# 07_AC97_AUDIO.net
KiCad netlist of a schematic drawn in Altium Designer
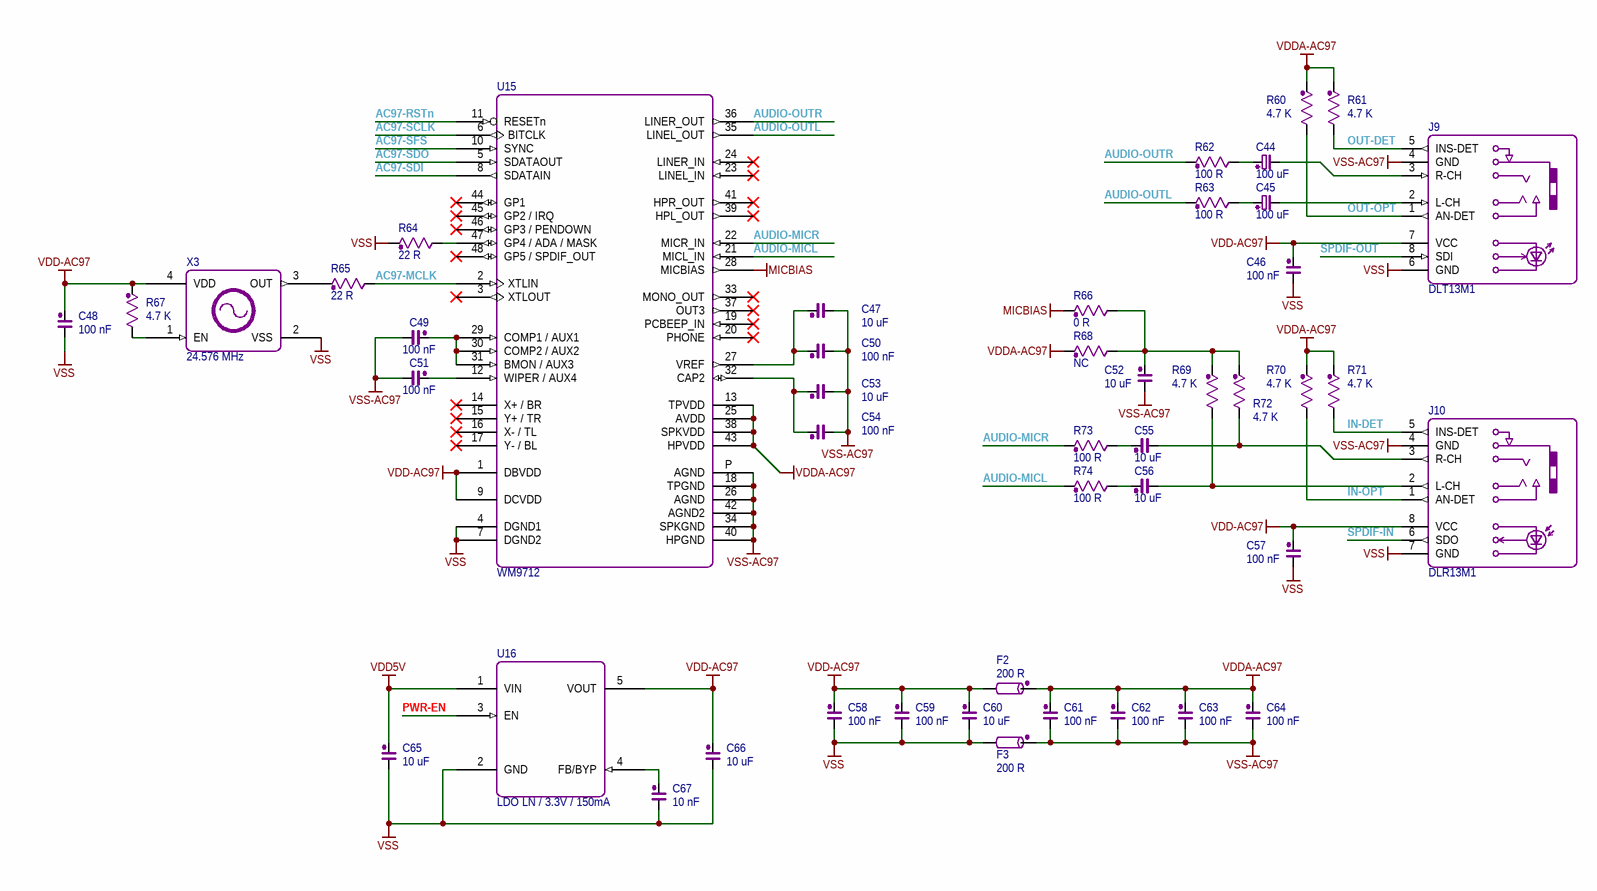
[diagram p0: 07_AC97_AUDIO.SchDoc]

(export (version "E")
  (design (tool "Eeschema 10.0.6"))
  (components
    (comp (ref "C44")
      (value "100 uF")
      (footprint "CAP_EB")
      (description "Electrolyte Capacitor")
      (fields
        (field (name "PARTNUMBER") "0")
        (field (name "DESIGNER") "shyul")
        (field (name "PUBLISHER") "Cowin")
      )
      (libsource (lib "Basc_1_Passive") (part "CAP_E"))
    )
    (comp (ref "C45")
      (value "100 uF")
      (footprint "CAP_EB")
      (description "Electrolyte Capacitor")
      (fields
        (field (name "PARTNUMBER") "0")
        (field (name "DESIGNER") "shyul")
        (field (name "PUBLISHER") "Cowin")
      )
      (libsource (lib "Basc_1_Passive") (part "CAP_E"))
    )
    (comp (ref "C46")
      (value "100 nF")
      (footprint "0603A1")
      (description "Normal Capacitor")
      (fields
        (field (name "PARTNUMBER") "0")
        (field (name "PUBLISHER") "Cowin")
        (field (name "DESIGNER") "shyul")
      )
      (libsource (lib "") (part "CAP_1"))
    )
    (comp (ref "C47")
      (value "10 uF")
      (footprint "0603A1")
      (description "Normal Capacitor")
      (fields
        (field (name "PARTNUMBER") "0")
        (field (name "PUBLISHER") "Cowin")
        (field (name "DESIGNER") "shyul")
      )
      (libsource (lib "Basc_1_Passive") (part "CAP"))
    )
    (comp (ref "C48")
      (value "100 nF")
      (footprint "0402A1")
      (description "Normal Capacitor")
      (fields
        (field (name "PARTNUMBER") "0")
        (field (name "PUBLISHER") "Cowin")
        (field (name "DESIGNER") "shyul")
      )
      (libsource (lib "") (part "CAP_1"))
    )
    (comp (ref "C49")
      (value "100 nF")
      (footprint "0402A1")
      (description "Normal Capacitor")
      (fields
        (field (name "PARTNUMBER") "0")
        (field (name "PUBLISHER") "Cowin")
        (field (name "DESIGNER") "shyul")
      )
      (libsource (lib "") (part "CAP_2"))
    )
    (comp (ref "C50")
      (value "100 nF")
      (footprint "0402A1")
      (description "Normal Capacitor")
      (fields
        (field (name "PARTNUMBER") "0")
        (field (name "PUBLISHER") "Cowin")
        (field (name "DESIGNER") "shyul")
      )
      (libsource (lib "Basc_1_Passive") (part "CAP"))
    )
    (comp (ref "C51")
      (value "100 nF")
      (footprint "0402A1")
      (description "Normal Capacitor")
      (fields
        (field (name "PARTNUMBER") "0")
        (field (name "PUBLISHER") "Cowin")
        (field (name "DESIGNER") "shyul")
      )
      (libsource (lib "") (part "CAP_2"))
    )
    (comp (ref "C52")
      (value "10 uF")
      (footprint "0603A1")
      (description "Normal Capacitor")
      (fields
        (field (name "PARTNUMBER") "0")
        (field (name "PUBLISHER") "Cowin")
        (field (name "DESIGNER") "shyul")
      )
      (libsource (lib "") (part "CAP_1"))
    )
    (comp (ref "C53")
      (value "10 uF")
      (footprint "0603A1")
      (description "Normal Capacitor")
      (fields
        (field (name "PARTNUMBER") "0")
        (field (name "PUBLISHER") "Cowin")
        (field (name "DESIGNER") "shyul")
      )
      (libsource (lib "Basc_1_Passive") (part "CAP"))
    )
    (comp (ref "C54")
      (value "100 nF")
      (footprint "0402A1")
      (description "Normal Capacitor")
      (fields
        (field (name "PARTNUMBER") "0")
        (field (name "PUBLISHER") "Cowin")
        (field (name "DESIGNER") "shyul")
      )
      (libsource (lib "Basc_1_Passive") (part "CAP"))
    )
    (comp (ref "C55")
      (value "10 uF")
      (footprint "1210A1")
      (description "Normal Capacitor")
      (fields
        (field (name "PARTNUMBER") "0")
        (field (name "PUBLISHER") "Cowin")
        (field (name "DESIGNER") "shyul")
      )
      (libsource (lib "Basc_1_Passive") (part "CAP"))
    )
    (comp (ref "C56")
      (value "10 uF")
      (footprint "1210A1")
      (description "Normal Capacitor")
      (fields
        (field (name "PARTNUMBER") "0")
        (field (name "PUBLISHER") "Cowin")
        (field (name "DESIGNER") "shyul")
      )
      (libsource (lib "Basc_1_Passive") (part "CAP"))
    )
    (comp (ref "C57")
      (value "100 nF")
      (footprint "0603A1")
      (description "Normal Capacitor")
      (fields
        (field (name "PARTNUMBER") "0")
        (field (name "PUBLISHER") "Cowin")
        (field (name "DESIGNER") "shyul")
      )
      (libsource (lib "") (part "CAP_1"))
    )
    (comp (ref "C58")
      (value "100 nF")
      (footprint "0402A1")
      (description "Normal Capacitor")
      (fields
        (field (name "PARTNUMBER") "0")
        (field (name "PUBLISHER") "Cowin")
        (field (name "DESIGNER") "shyul")
      )
      (libsource (lib "") (part "CAP_1"))
    )
    (comp (ref "C59")
      (value "100 nF")
      (footprint "0402A1")
      (description "Normal Capacitor")
      (fields
        (field (name "PARTNUMBER") "0")
        (field (name "PUBLISHER") "Cowin")
        (field (name "DESIGNER") "shyul")
      )
      (libsource (lib "") (part "CAP_1"))
    )
    (comp (ref "C60")
      (value "10 uF")
      (footprint "0603A1")
      (description "Normal Capacitor")
      (fields
        (field (name "PARTNUMBER") "0")
        (field (name "PUBLISHER") "Cowin")
        (field (name "DESIGNER") "shyul")
      )
      (libsource (lib "") (part "CAP_1"))
    )
    (comp (ref "C61")
      (value "100 nF")
      (footprint "0402A1")
      (description "Normal Capacitor")
      (fields
        (field (name "PARTNUMBER") "0")
        (field (name "PUBLISHER") "Cowin")
        (field (name "DESIGNER") "shyul")
      )
      (libsource (lib "") (part "CAP_1"))
    )
    (comp (ref "C62")
      (value "100 nF")
      (footprint "0402A1")
      (description "Normal Capacitor")
      (fields
        (field (name "PARTNUMBER") "0")
        (field (name "PUBLISHER") "Cowin")
        (field (name "DESIGNER") "shyul")
      )
      (libsource (lib "") (part "CAP_1"))
    )
    (comp (ref "C63")
      (value "100 nF")
      (footprint "0402A1")
      (description "Normal Capacitor")
      (fields
        (field (name "PARTNUMBER") "0")
        (field (name "PUBLISHER") "Cowin")
        (field (name "DESIGNER") "shyul")
      )
      (libsource (lib "") (part "CAP_1"))
    )
    (comp (ref "C64")
      (value "100 nF")
      (footprint "0402A1")
      (description "Normal Capacitor")
      (fields
        (field (name "PARTNUMBER") "0")
        (field (name "PUBLISHER") "Cowin")
        (field (name "DESIGNER") "shyul")
      )
      (libsource (lib "") (part "CAP_1"))
    )
    (comp (ref "C65")
      (value "10 uF")
      (footprint "0603A1")
      (description "Normal Capacitor")
      (fields
        (field (name "PARTNUMBER") "0")
        (field (name "PUBLISHER") "Cowin")
        (field (name "DESIGNER") "shyul")
      )
      (libsource (lib "") (part "CAP_1"))
    )
    (comp (ref "C66")
      (value "10 uF")
      (footprint "0603A1")
      (description "Normal Capacitor")
      (fields
        (field (name "PARTNUMBER") "0")
        (field (name "PUBLISHER") "Cowin")
        (field (name "DESIGNER") "shyul")
      )
      (libsource (lib "") (part "CAP_1"))
    )
    (comp (ref "C67")
      (value "10 nF")
      (footprint "0402A1")
      (description "Normal Capacitor")
      (fields
        (field (name "PARTNUMBER") "0")
        (field (name "PUBLISHER") "Cowin")
        (field (name "DESIGNER") "shyul")
      )
      (libsource (lib "") (part "CAP_1"))
    )
    (comp (ref "F2")
      (value "200 R")
      (footprint "0603A3")
      (description "EMI Bead")
      (fields
        (field (name "PARTNUMBER") "BLM")
        (field (name "DESIGNER") "shyul")
        (field (name "PUBLISHER") "Cowin")
      )
      (libsource (lib "Basc_2_EMI_Protection") (part "BEAD"))
    )
    (comp (ref "F3")
      (value "200 R")
      (footprint "0603A3")
      (description "EMI Bead")
      (fields
        (field (name "PARTNUMBER") "BLM")
        (field (name "DESIGNER") "shyul")
        (field (name "PUBLISHER") "Cowin")
      )
      (libsource (lib "Basc_2_EMI_Protection") (part "BEAD"))
    )
    (comp (ref "J9")
      (value "DLT13M1")
      (footprint "DLT13M1")
      (description "3.5mm Audio Jack with SPDIF Optical Output")
      (fields (field (name "PUBLISHER") "Cowin") (field (name "DESIGNER") "shyul"))
      (libsource (lib "PCB_MDB-U01") (part "DLT13M1"))
    )
    (comp (ref "J10")
      (value "DLR13M1")
      (footprint "DLR13M1")
      (description "3.5mm Audio Jack with SPDIF Optical Input")
      (fields (field (name "PUBLISHER") "Cowin") (field (name "DESIGNER") "shyul"))
      (libsource (lib "PCB_MDB-U01") (part "DLR13M1"))
    )
    (comp (ref "R60")
      (value "4.7 K")
      (footprint "0603A2")
      (description "Normal Resistor")
      (fields
        (field (name "PARTNUMBER") "0")
        (field (name "DESIGNER") "shyul")
        (field (name "PUBLISHER") "Cowin")
      )
      (libsource (lib "Basc_1_Passive") (part "RES"))
    )
    (comp (ref "R61")
      (value "4.7 K")
      (footprint "0603A2")
      (description "Normal Resistor")
      (fields
        (field (name "PARTNUMBER") "0")
        (field (name "DESIGNER") "shyul")
        (field (name "PUBLISHER") "Cowin")
      )
      (libsource (lib "Basc_1_Passive") (part "RES"))
    )
    (comp (ref "R62")
      (value "100 R")
      (footprint "0603A2")
      (description "Normal Resistor")
      (fields
        (field (name "PARTNUMBER") "0")
        (field (name "DESIGNER") "shyul")
        (field (name "PUBLISHER") "Cowin")
      )
      (libsource (lib "Basc_1_Passive") (part "RES"))
    )
    (comp (ref "R63")
      (value "100 R")
      (footprint "0603A2")
      (description "Normal Resistor")
      (fields
        (field (name "PARTNUMBER") "0")
        (field (name "DESIGNER") "shyul")
        (field (name "PUBLISHER") "Cowin")
      )
      (libsource (lib "Basc_1_Passive") (part "RES"))
    )
    (comp (ref "R64")
      (value "22 R")
      (footprint "0402A2")
      (description "Normal Resistor")
      (fields
        (field (name "PARTNUMBER") "0")
        (field (name "DESIGNER") "shyul")
        (field (name "PUBLISHER") "Cowin")
      )
      (libsource (lib "Basc_1_Passive") (part "RES"))
    )
    (comp (ref "R65")
      (value "22 R")
      (footprint "0402A2")
      (description "Normal Resistor")
      (fields
        (field (name "PARTNUMBER") "0")
        (field (name "DESIGNER") "shyul")
        (field (name "PUBLISHER") "Cowin")
      )
      (libsource (lib "Basc_1_Passive") (part "RES"))
    )
    (comp (ref "R66")
      (value "0 R")
      (footprint "0603A2")
      (description "Normal Resistor")
      (fields
        (field (name "PARTNUMBER") "0")
        (field (name "DESIGNER") "shyul")
        (field (name "PUBLISHER") "Cowin")
      )
      (libsource (lib "Basc_1_Passive") (part "RES"))
    )
    (comp (ref "R67")
      (value "4.7 K")
      (footprint "0402A2")
      (description "Normal Resistor")
      (fields
        (field (name "PARTNUMBER") "0")
        (field (name "DESIGNER") "shyul")
        (field (name "PUBLISHER") "Cowin")
      )
      (libsource (lib "Basc_1_Passive") (part "RES"))
    )
    (comp (ref "R68")
      (value "NC")
      (footprint "0603A2")
      (description "Normal Resistor")
      (fields
        (field (name "PARTNUMBER") "0")
        (field (name "DESIGNER") "shyul")
        (field (name "PUBLISHER") "Cowin")
      )
      (libsource (lib "Basc_1_Passive") (part "RES"))
    )
    (comp (ref "R69")
      (value "4.7 K")
      (footprint "0603A2")
      (description "Normal Resistor")
      (fields
        (field (name "PARTNUMBER") "0")
        (field (name "DESIGNER") "shyul")
        (field (name "PUBLISHER") "Cowin")
      )
      (libsource (lib "Basc_1_Passive") (part "RES"))
    )
    (comp (ref "R70")
      (value "4.7 K")
      (footprint "0603A2")
      (description "Normal Resistor")
      (fields
        (field (name "PARTNUMBER") "0")
        (field (name "DESIGNER") "shyul")
        (field (name "PUBLISHER") "Cowin")
      )
      (libsource (lib "Basc_1_Passive") (part "RES"))
    )
    (comp (ref "R71")
      (value "4.7 K")
      (footprint "0603A2")
      (description "Normal Resistor")
      (fields
        (field (name "PARTNUMBER") "0")
        (field (name "DESIGNER") "shyul")
        (field (name "PUBLISHER") "Cowin")
      )
      (libsource (lib "Basc_1_Passive") (part "RES"))
    )
    (comp (ref "R72")
      (value "4.7 K")
      (footprint "0603A2")
      (description "Normal Resistor")
      (fields
        (field (name "PARTNUMBER") "0")
        (field (name "DESIGNER") "shyul")
        (field (name "PUBLISHER") "Cowin")
      )
      (libsource (lib "Basc_1_Passive") (part "RES"))
    )
    (comp (ref "R73")
      (value "100 R")
      (footprint "0603A2")
      (description "Normal Resistor")
      (fields
        (field (name "PARTNUMBER") "0")
        (field (name "DESIGNER") "shyul")
        (field (name "PUBLISHER") "Cowin")
      )
      (libsource (lib "Basc_1_Passive") (part "RES"))
    )
    (comp (ref "R74")
      (value "100 R")
      (footprint "0603A2")
      (description "Normal Resistor")
      (fields
        (field (name "PARTNUMBER") "0")
        (field (name "DESIGNER") "shyul")
        (field (name "PUBLISHER") "Cowin")
      )
      (libsource (lib "Basc_1_Passive") (part "RES"))
    )
    (comp (ref "U15")
      (value "WM9712")
      (footprint "QFN-7-48")
      (description "WM9712 AC97 Codec")
      (fields
        (field (name "PARTNUMBER") "WM9712LGEFL")
        (field (name "PUBLISHER") "Cowin")
        (field (name "DESIGNER") "shyul")
      )
      (libsource (lib "PCB_LDB-U01") (part "WM9712"))
    )
    (comp (ref "U16")
      (value "LDO LN / 3.3V / 150mA")
      (footprint "SOT-23-5")
      (description "Low Noise LDO 150mA")
      (fields
        (field (name "PARTNUMBER") "MIC5265-3.3YD5")
        (field (name "PUBLISHER") "Cowin")
        (field (name "DESIGNER") "shyul")
      )
      (libsource (lib "IC_10_Regulator") (part "MIC5265"))
    )
    (comp (ref "X3")
      (value "24.576 MHz")
      (footprint "OSC_4B_S_5032")
      (description "Crystal Oscillator")
      (fields
        (field (name "PARTNUMBER") "0")
        (field (name "PUBLISHER") "Cowin")
        (field (name "DESIGNER") "shyul")
      )
      (libsource (lib "Basc_4_Other") (part "OSC_4B"))
    )
  )
  (nets
    (net (code "1") (name "/AC97-MCLK") (class "Default")
      (node (ref "R65") (pin "1") (pinfunction "1_1") (pintype "passive"))
      (node (ref "U15") (pin "2") (pinfunction "XTLIN_2") (pintype "input"))
    )
    (net (code "2") (name "/AC97-RSTn") (class "Default")
      (node (ref "U15") (pin "11") (pinfunction "RESETn_11") (pintype "input"))
    )
    (net (code "3") (name "/AC97-SCLK") (class "Default")
      (node (ref "U15") (pin "6") (pinfunction "BITCLK_6") (pintype "output"))
    )
    (net (code "4") (name "/AC97-SDI") (class "Default")
      (node (ref "U15") (pin "8") (pinfunction "SDATAIN_8") (pintype "output"))
    )
    (net (code "5") (name "/AC97-SDO") (class "Default")
      (node (ref "U15") (pin "5") (pinfunction "SDATAOUT_5") (pintype "input"))
    )
    (net (code "6") (name "/AC97-SFS") (class "Default")
      (node (ref "U15") (pin "10") (pinfunction "SYNC_10") (pintype "input"))
    )
    (net (code "7") (name "/AUDIO-MICL") (class "Default")
      (node (ref "R74") (pin "2") (pinfunction "2_2") (pintype "passive"))
      (node (ref "U15") (pin "21") (pinfunction "MICL_IN_21") (pintype "input"))
    )
    (net (code "8") (name "/AUDIO-MICR") (class "Default")
      (node (ref "R73") (pin "2") (pinfunction "2_2") (pintype "passive"))
      (node (ref "U15") (pin "22") (pinfunction "MICR_IN_22") (pintype "input"))
    )
    (net (code "9") (name "/AUDIO-OUTL") (class "Default")
      (node (ref "R63") (pin "2") (pinfunction "2_2") (pintype "passive"))
      (node (ref "U15") (pin "35") (pinfunction "LINEL_OUT_35") (pintype "output"))
    )
    (net (code "10") (name "/AUDIO-OUTR") (class "Default")
      (node (ref "R62") (pin "2") (pinfunction "2_2") (pintype "passive"))
      (node (ref "U15") (pin "36") (pinfunction "LINER_OUT_36") (pintype "output"))
    )
    (net (code "11") (name "/IN-DET") (class "Default")
      (node (ref "J10") (pin "5") (pinfunction "INS-DET_5") (pintype "output"))
      (node (ref "R71") (pin "1") (pinfunction "1_1") (pintype "passive"))
    )
    (net (code "12") (name "/IN-OPT") (class "Default")
      (node (ref "J10") (pin "1") (pinfunction "AN-DET_1") (pintype "output"))
      (node (ref "R70") (pin "1") (pinfunction "1_1") (pintype "passive"))
    )
    (net (code "13") (name "/OUT-DET") (class "Default")
      (node (ref "J9") (pin "5") (pinfunction "INS-DET_5") (pintype "output"))
      (node (ref "R61") (pin "1") (pinfunction "1_1") (pintype "passive"))
    )
    (net (code "14") (name "/OUT-OPT") (class "Default")
      (node (ref "J9") (pin "1") (pinfunction "AN-DET_1") (pintype "output"))
      (node (ref "R60") (pin "1") (pinfunction "1_1") (pintype "passive"))
    )
    (net (code "15") (name "/PWR-EN") (class "Default")
      (node (ref "U16") (pin "3") (pinfunction "EN_3") (pintype "input"))
    )
    (net (code "16") (name "/SPDIF-IN") (class "Default")
      (node (ref "J10") (pin "6") (pinfunction "SDO_6") (pintype "output"))
    )
    (net (code "17") (name "/SPDIF-OUT") (class "Default")
      (node (ref "J9") (pin "8") (pinfunction "SDI_8") (pintype "input"))
    )
    (net (code "18") (name "MICBIAS") (class "Default")
      (node (ref "R66") (pin "2") (pinfunction "2_2") (pintype "passive"))
      (node (ref "U15") (pin "28") (pinfunction "MICBIAS_28") (pintype "output"))
    )
    (net (code "19") (name "Net-(C44-Pad2)") (class "Default")
      (node (ref "C44") (pin "2") (pinfunction "2_2") (pintype "passive"))
      (node (ref "R62") (pin "1") (pinfunction "1_1") (pintype "passive"))
    )
    (net (code "20") (name "Net-(C45-Pad2)") (class "Default")
      (node (ref "C45") (pin "2") (pinfunction "2_2") (pintype "passive"))
      (node (ref "R63") (pin "1") (pinfunction "1_1") (pintype "passive"))
    )
    (net (code "21") (name "Net-(C52-Pad2)") (class "Default")
      (node (ref "C52") (pin "2") (pinfunction "2_2") (pintype "passive"))
      (node (ref "R66") (pin "1") (pinfunction "1_1") (pintype "passive"))
      (node (ref "R68") (pin "1") (pinfunction "1_1") (pintype "passive"))
      (node (ref "R69") (pin "2") (pinfunction "2_2") (pintype "passive"))
      (node (ref "R72") (pin "2") (pinfunction "2_2") (pintype "passive"))
    )
    (net (code "22") (name "Net-(C55-Pad2)") (class "Default")
      (node (ref "C55") (pin "2") (pinfunction "2_2") (pintype "passive"))
      (node (ref "R73") (pin "1") (pinfunction "1_1") (pintype "passive"))
    )
    (net (code "23") (name "Net-(C56-Pad2)") (class "Default")
      (node (ref "C56") (pin "2") (pinfunction "2_2") (pintype "passive"))
      (node (ref "R74") (pin "1") (pinfunction "1_1") (pintype "passive"))
    )
    (net (code "24") (name "Net-(J9-L-CH)") (class "Default")
      (node (ref "C45") (pin "1") (pinfunction "1_1") (pintype "passive"))
      (node (ref "J9") (pin "2") (pinfunction "L-CH_2") (pintype "input"))
    )
    (net (code "25") (name "Net-(J9-R-CH)") (class "Default")
      (node (ref "C44") (pin "1") (pinfunction "1_1") (pintype "passive"))
      (node (ref "J9") (pin "3") (pinfunction "R-CH_3") (pintype "input"))
    )
    (net (code "26") (name "Net-(J10-L-CH)") (class "Default")
      (node (ref "C56") (pin "1") (pinfunction "1_1") (pintype "passive"))
      (node (ref "J10") (pin "2") (pinfunction "L-CH_2") (pintype "output"))
      (node (ref "R69") (pin "1") (pinfunction "1_1") (pintype "passive"))
    )
    (net (code "27") (name "Net-(J10-R-CH)") (class "Default")
      (node (ref "C55") (pin "1") (pinfunction "1_1") (pintype "passive"))
      (node (ref "J10") (pin "3") (pinfunction "R-CH_3") (pintype "output"))
      (node (ref "R72") (pin "1") (pinfunction "1_1") (pintype "passive"))
    )
    (net (code "28") (name "Net-(U15-BMON_{slash}_AUX3)") (class "Default")
      (node (ref "C49") (pin "2") (pinfunction "2_2") (pintype "passive"))
      (node (ref "U15") (pin "29") (pinfunction "COMP1_/_AUX1_29") (pintype "input"))
      (node (ref "U15") (pin "30") (pinfunction "COMP2_/_AUX2_30") (pintype "input"))
      (node (ref "U15") (pin "31") (pinfunction "BMON_/_AUX3_31") (pintype "input"))
    )
    (net (code "29") (name "Net-(U15-CAP2)") (class "Default")
      (node (ref "C53") (pin "2") (pinfunction "2_2") (pintype "passive"))
      (node (ref "C54") (pin "2") (pinfunction "2_2") (pintype "passive"))
      (node (ref "U15") (pin "32") (pinfunction "CAP2_32") (pintype "bidirectional"))
    )
    (net (code "30") (name "Net-(U15-GP4_{slash}_ADA_{slash}_MASK)") (class "Default")
      (node (ref "R64") (pin "1") (pinfunction "1_1") (pintype "passive"))
      (node (ref "U15") (pin "47") (pinfunction "GP4_/_ADA_/_MASK_47") (pintype "bidirectional"))
    )
    (net (code "31") (name "Net-(U15-VREF)") (class "Default")
      (node (ref "C47") (pin "2") (pinfunction "2_2") (pintype "passive"))
      (node (ref "C50") (pin "2") (pinfunction "2_2") (pintype "passive"))
      (node (ref "U15") (pin "27") (pinfunction "VREF_27") (pintype "output"))
    )
    (net (code "32") (name "Net-(U15-WIPER_{slash}_AUX4)") (class "Default")
      (node (ref "C51") (pin "2") (pinfunction "2_2") (pintype "passive"))
      (node (ref "U15") (pin "12") (pinfunction "WIPER_/_AUX4_12") (pintype "input"))
    )
    (net (code "33") (name "Net-(U16-FB{slash}BYP)") (class "Default")
      (node (ref "C67") (pin "2") (pinfunction "2_2") (pintype "passive"))
      (node (ref "U16") (pin "4") (pinfunction "FB/BYP_4") (pintype "input"))
    )
    (net (code "34") (name "Net-(X3-EN)") (class "Default")
      (node (ref "R67") (pin "1") (pinfunction "1_1") (pintype "passive"))
      (node (ref "X3") (pin "1") (pinfunction "EN_1") (pintype "input"))
    )
    (net (code "35") (name "Net-(X3-OUT)") (class "Default")
      (node (ref "R65") (pin "2") (pinfunction "2_2") (pintype "passive"))
      (node (ref "X3") (pin "3") (pinfunction "OUT_3") (pintype "output"))
    )
    (net (code "36") (name "VDD-AC97") (class "Default")
      (node (ref "C46") (pin "2") (pinfunction "2_2") (pintype "passive"))
      (node (ref "C48") (pin "2") (pinfunction "2_2") (pintype "passive"))
      (node (ref "C57") (pin "2") (pinfunction "2_2") (pintype "passive"))
      (node (ref "C58") (pin "2") (pinfunction "2_2") (pintype "passive"))
      (node (ref "C59") (pin "2") (pinfunction "2_2") (pintype "passive"))
      (node (ref "C60") (pin "2") (pinfunction "2_2") (pintype "passive"))
      (node (ref "C66") (pin "2") (pinfunction "2_2") (pintype "passive"))
      (node (ref "F2") (pin "1") (pinfunction "1_1") (pintype "passive"))
      (node (ref "J10") (pin "8") (pinfunction "VCC_8") (pintype "passive"))
      (node (ref "J9") (pin "7") (pinfunction "VCC_7") (pintype "passive"))
      (node (ref "R67") (pin "2") (pinfunction "2_2") (pintype "passive"))
      (node (ref "U15") (pin "1") (pinfunction "DBVDD_1") (pintype "passive"))
      (node (ref "U15") (pin "9") (pinfunction "DCVDD_9") (pintype "passive"))
      (node (ref "U16") (pin "5") (pinfunction "VOUT_5") (pintype "power_in"))
      (node (ref "X3") (pin "4") (pinfunction "VDD_4") (pintype "power_in"))
    )
    (net (code "37") (name "VDD5V") (class "Default")
      (node (ref "C65") (pin "2") (pinfunction "2_2") (pintype "passive"))
      (node (ref "U16") (pin "1") (pinfunction "VIN_1") (pintype "power_in"))
    )
    (net (code "38") (name "VDDA-AC97") (class "Default")
      (node (ref "C61") (pin "2") (pinfunction "2_2") (pintype "passive"))
      (node (ref "C62") (pin "2") (pinfunction "2_2") (pintype "passive"))
      (node (ref "C63") (pin "2") (pinfunction "2_2") (pintype "passive"))
      (node (ref "C64") (pin "2") (pinfunction "2_2") (pintype "passive"))
      (node (ref "F2") (pin "2") (pinfunction "2_2") (pintype "passive"))
      (node (ref "R60") (pin "2") (pinfunction "2_2") (pintype "passive"))
      (node (ref "R61") (pin "2") (pinfunction "2_2") (pintype "passive"))
      (node (ref "R68") (pin "2") (pinfunction "2_2") (pintype "passive"))
      (node (ref "R70") (pin "2") (pinfunction "2_2") (pintype "passive"))
      (node (ref "R71") (pin "2") (pinfunction "2_2") (pintype "passive"))
      (node (ref "U15") (pin "13") (pinfunction "TPVDD_13") (pintype "passive"))
      (node (ref "U15") (pin "25") (pinfunction "AVDD_25") (pintype "passive"))
      (node (ref "U15") (pin "38") (pinfunction "SPKVDD_38") (pintype "passive"))
      (node (ref "U15") (pin "43") (pinfunction "HPVDD_43") (pintype "passive"))
    )
    (net (code "39") (name "VSS") (class "Default")
      (node (ref "C46") (pin "1") (pinfunction "1_1") (pintype "passive"))
      (node (ref "C48") (pin "1") (pinfunction "1_1") (pintype "passive"))
      (node (ref "C57") (pin "1") (pinfunction "1_1") (pintype "passive"))
      (node (ref "C58") (pin "1") (pinfunction "1_1") (pintype "passive"))
      (node (ref "C59") (pin "1") (pinfunction "1_1") (pintype "passive"))
      (node (ref "C60") (pin "1") (pinfunction "1_1") (pintype "passive"))
      (node (ref "C65") (pin "1") (pinfunction "1_1") (pintype "passive"))
      (node (ref "C66") (pin "1") (pinfunction "1_1") (pintype "passive"))
      (node (ref "C67") (pin "1") (pinfunction "1_1") (pintype "passive"))
      (node (ref "F3") (pin "1") (pinfunction "1_1") (pintype "passive"))
      (node (ref "J10") (pin "7") (pinfunction "GND_7") (pintype "passive"))
      (node (ref "J9") (pin "6") (pinfunction "GND_6") (pintype "passive"))
      (node (ref "R64") (pin "2") (pinfunction "2_2") (pintype "passive"))
      (node (ref "U15") (pin "4") (pinfunction "DGND1_4") (pintype "passive"))
      (node (ref "U15") (pin "7") (pinfunction "DGND2_7") (pintype "passive"))
      (node (ref "U16") (pin "2") (pinfunction "GND_2") (pintype "power_in"))
      (node (ref "X3") (pin "2") (pinfunction "VSS_2") (pintype "power_in"))
    )
    (net (code "40") (name "VSS-AC97") (class "Default")
      (node (ref "C47") (pin "1") (pinfunction "1_1") (pintype "passive"))
      (node (ref "C49") (pin "1") (pinfunction "1_1") (pintype "passive"))
      (node (ref "C50") (pin "1") (pinfunction "1_1") (pintype "passive"))
      (node (ref "C51") (pin "1") (pinfunction "1_1") (pintype "passive"))
      (node (ref "C52") (pin "1") (pinfunction "1_1") (pintype "passive"))
      (node (ref "C53") (pin "1") (pinfunction "1_1") (pintype "passive"))
      (node (ref "C54") (pin "1") (pinfunction "1_1") (pintype "passive"))
      (node (ref "C61") (pin "1") (pinfunction "1_1") (pintype "passive"))
      (node (ref "C62") (pin "1") (pinfunction "1_1") (pintype "passive"))
      (node (ref "C63") (pin "1") (pinfunction "1_1") (pintype "passive"))
      (node (ref "C64") (pin "1") (pinfunction "1_1") (pintype "passive"))
      (node (ref "F3") (pin "2") (pinfunction "2_2") (pintype "passive"))
      (node (ref "J10") (pin "4") (pinfunction "GND_4") (pintype "passive"))
      (node (ref "J9") (pin "4") (pinfunction "GND_4") (pintype "passive"))
      (node (ref "U15") (pin "18") (pinfunction "TPGND_18") (pintype "passive"))
      (node (ref "U15") (pin "26") (pinfunction "AGND_26") (pintype "passive"))
      (node (ref "U15") (pin "34") (pinfunction "SPKGND_34") (pintype "passive"))
      (node (ref "U15") (pin "40") (pinfunction "HPGND_40") (pintype "passive"))
      (node (ref "U15") (pin "42") (pinfunction "AGND2_42") (pintype "passive"))
      (node (ref "U15") (pin "P") (pinfunction "AGND_P") (pintype "passive"))
    )
    (net (code "41") (name "unconnected-(U15-GP1-Pad44)") (class "Default")
      (node (ref "U15") (pin "44") (pinfunction "GP1_44") (pintype "bidirectional+no_connect"))
    )
    (net (code "42") (name "unconnected-(U15-GP2_{slash}_IRQ-Pad45)") (class "Default")
      (node (ref "U15") (pin "45") (pinfunction "GP2_/_IRQ_45") (pintype "bidirectional+no_connect"))
    )
    (net (code "43") (name "unconnected-(U15-GP3_{slash}_PENDOWN-Pad46)") (class "Default")
      (node (ref "U15") (pin "46") (pinfunction "GP3_/_PENDOWN_46") (pintype "bidirectional+no_connect"))
    )
    (net (code "44") (name "unconnected-(U15-GP5_{slash}_SPDIF_OUT-Pad48)") (class "Default")
      (node (ref "U15") (pin "48") (pinfunction "GP5_/_SPDIF_OUT_48") (pintype "bidirectional+no_connect"))
    )
    (net (code "45") (name "unconnected-(U15-HPL_OUT-Pad39)") (class "Default")
      (node (ref "U15") (pin "39") (pinfunction "HPL_OUT_39") (pintype "output+no_connect"))
    )
    (net (code "46") (name "unconnected-(U15-HPR_OUT-Pad41)") (class "Default")
      (node (ref "U15") (pin "41") (pinfunction "HPR_OUT_41") (pintype "output+no_connect"))
    )
    (net (code "47") (name "unconnected-(U15-LINEL_IN-Pad23)") (class "Default")
      (node (ref "U15") (pin "23") (pinfunction "LINEL_IN_23") (pintype "input+no_connect"))
    )
    (net (code "48") (name "unconnected-(U15-LINER_IN-Pad24)") (class "Default")
      (node (ref "U15") (pin "24") (pinfunction "LINER_IN_24") (pintype "input+no_connect"))
    )
    (net (code "49") (name "unconnected-(U15-MONO_OUT-Pad33)") (class "Default")
      (node (ref "U15") (pin "33") (pinfunction "MONO_OUT_33") (pintype "output+no_connect"))
    )
    (net (code "50") (name "unconnected-(U15-OUT3-Pad37)") (class "Default")
      (node (ref "U15") (pin "37") (pinfunction "OUT3_37") (pintype "output+no_connect"))
    )
    (net (code "51") (name "unconnected-(U15-PCBEEP_IN-Pad19)") (class "Default")
      (node (ref "U15") (pin "19") (pinfunction "PCBEEP_IN_19") (pintype "input+no_connect"))
    )
    (net (code "52") (name "unconnected-(U15-PHONE-Pad20)") (class "Default")
      (node (ref "U15") (pin "20") (pinfunction "PHONE_20") (pintype "input+no_connect"))
    )
    (net (code "53") (name "unconnected-(U15-X+_{slash}_BR-Pad14)") (class "Default")
      (node (ref "U15") (pin "14") (pinfunction "X+_/_BR_14") (pintype "passive+no_connect"))
    )
    (net (code "54") (name "unconnected-(U15-X-_{slash}_TL-Pad16)") (class "Default")
      (node (ref "U15") (pin "16") (pinfunction "X-_/_TL_16") (pintype "passive+no_connect"))
    )
    (net (code "55") (name "unconnected-(U15-XTLOUT-Pad3)") (class "Default")
      (node (ref "U15") (pin "3") (pinfunction "XTLOUT_3") (pintype "output+no_connect"))
    )
    (net (code "56") (name "unconnected-(U15-Y+_{slash}_TR-Pad15)") (class "Default")
      (node (ref "U15") (pin "15") (pinfunction "Y+_/_TR_15") (pintype "passive+no_connect"))
    )
    (net (code "57") (name "unconnected-(U15-Y-_{slash}_BL-Pad17)") (class "Default")
      (node (ref "U15") (pin "17") (pinfunction "Y-_/_BL_17") (pintype "passive+no_connect"))
    )
  )
)
